# 3_esc_power_sw.net
KiCad netlist of a schematic drawn in Altium Designer
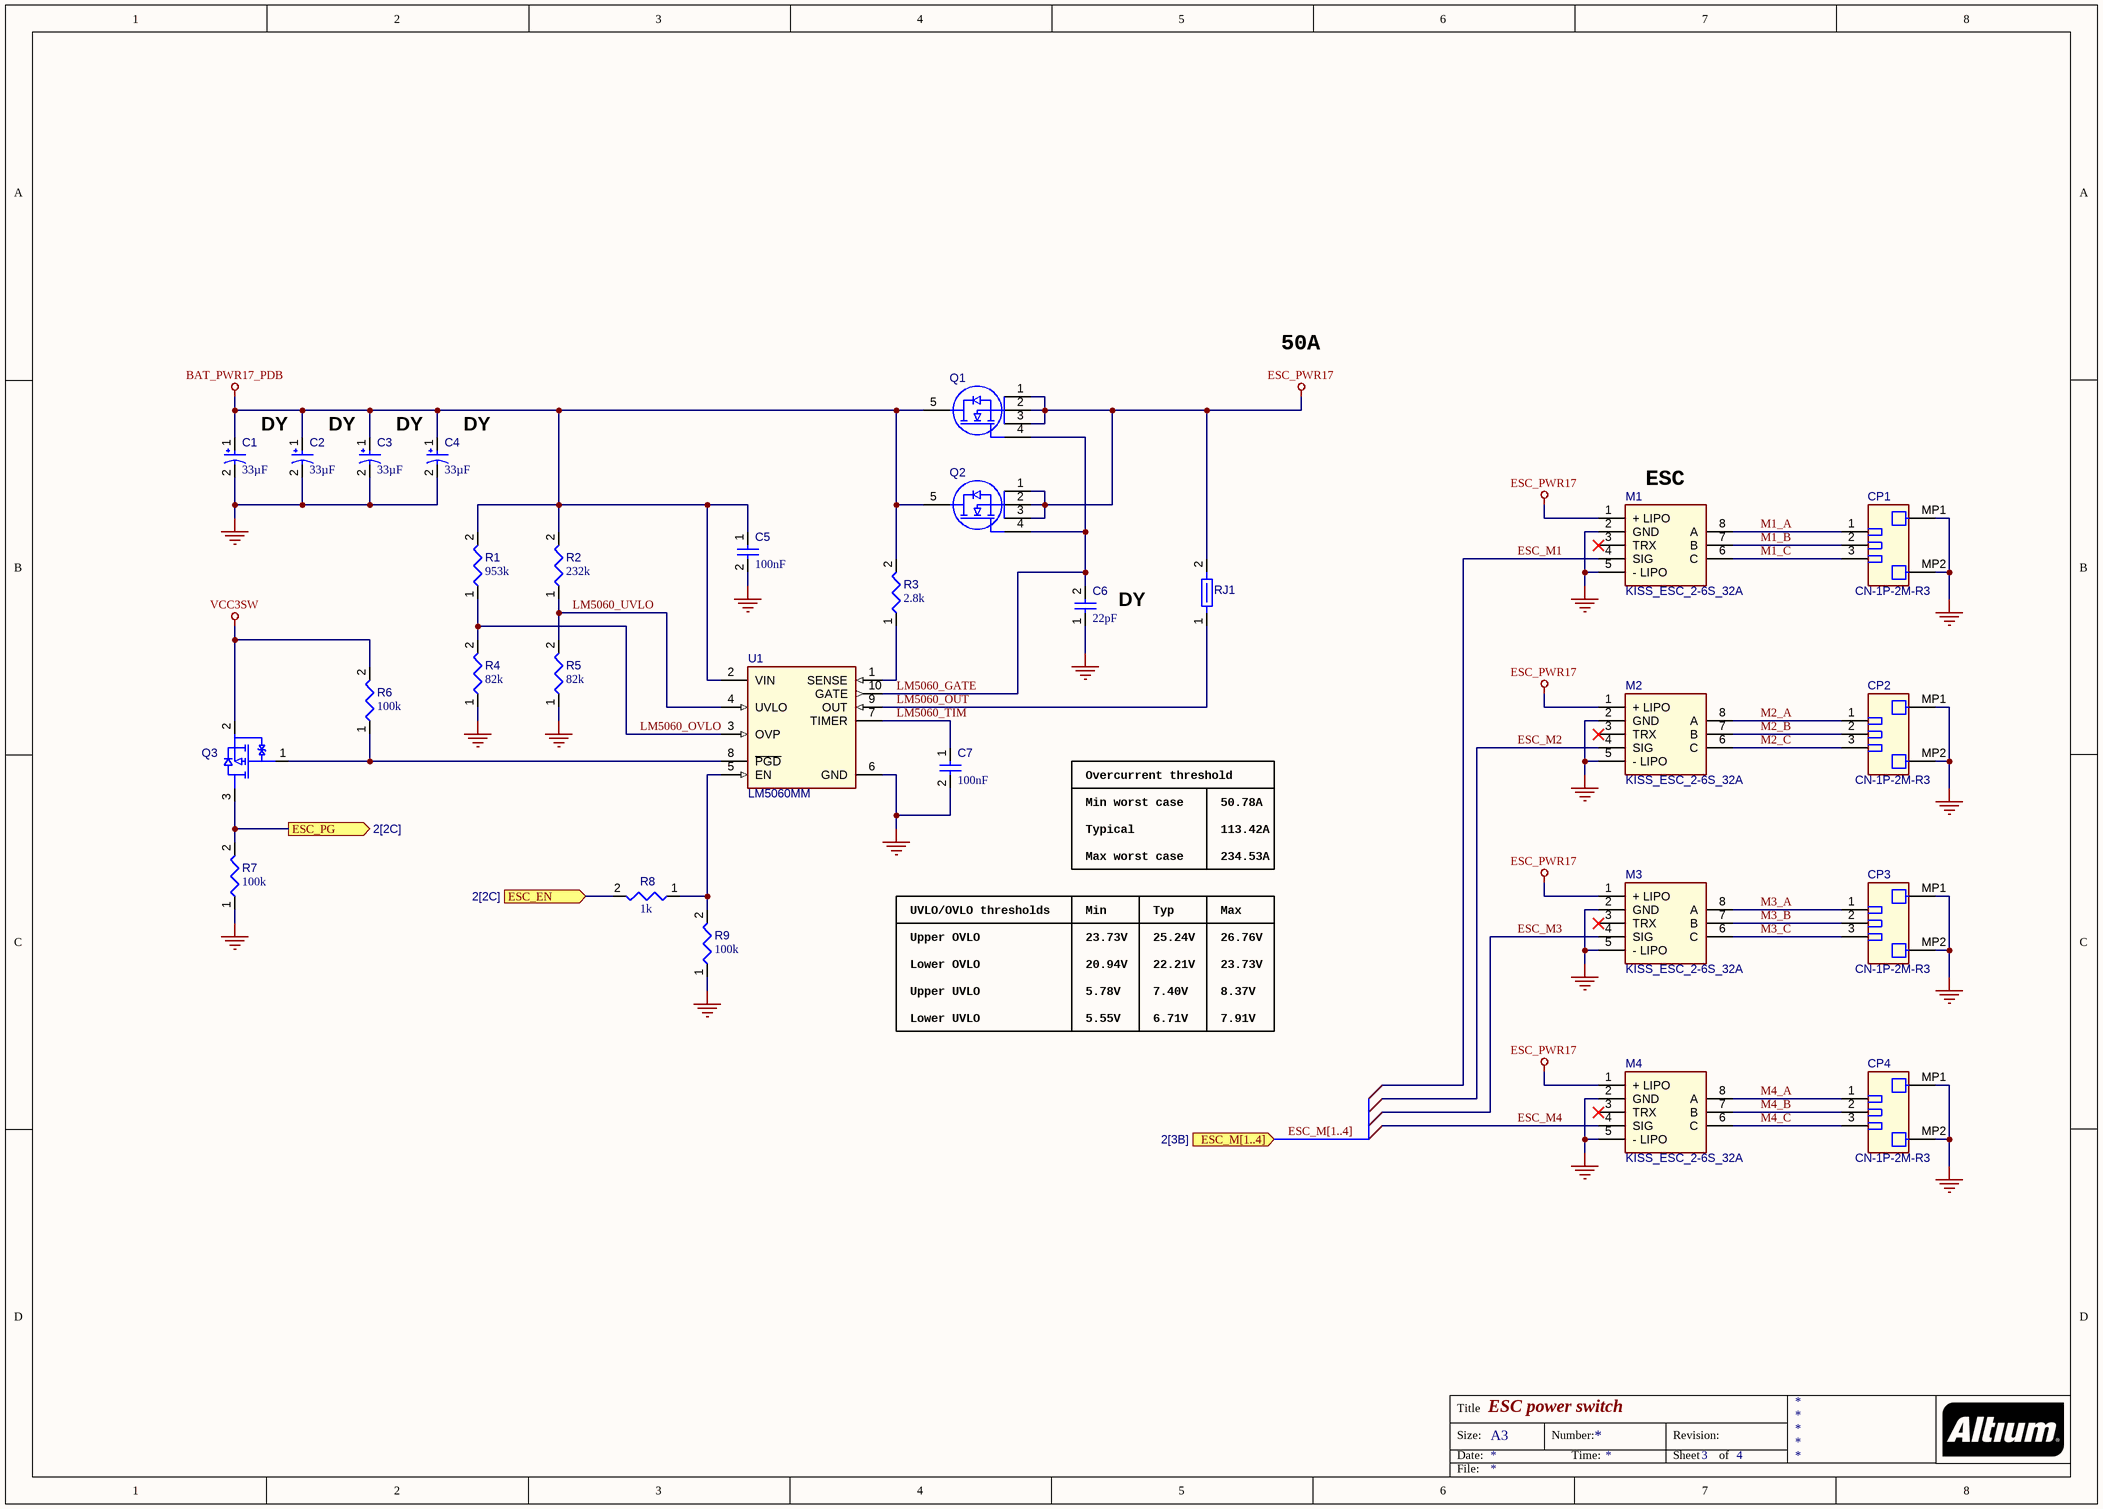
[diagram p0: 3_esc_power_sw.SchDoc]

(export (version "E")
  (design (tool "Eeschema 10.0.6"))
  (components
    (comp (ref "C1")
      (value "33µF")
      (footprint "EEF-CX1E330R-Footprint-1")
      (description "Aluminum Organic Polymer Capacitors 33uF 25volt SP-Cap AEC-Q200")
      (fields (field (name "TOLERANCE") "20%") (field (name "Comment") "Capacitor 33µF +/-20% 25V 2917"))
      (libsource (lib "<Company> Server") (part "CAP-P-2"))
    )
    (comp (ref "C2")
      (value "33µF")
      (footprint "EEF-CX1E330R-Footprint-1")
      (description "Aluminum Organic Polymer Capacitors 33uF 25volt SP-Cap AEC-Q200")
      (fields (field (name "TOLERANCE") "20%") (field (name "Comment") "Capacitor 33µF +/-20% 25V 2917"))
      (libsource (lib "<Company> Server") (part "CAP-P-2"))
    )
    (comp (ref "C3")
      (value "33µF")
      (footprint "EEF-CX1E330R-Footprint-1")
      (description "Aluminum Organic Polymer Capacitors 33uF 25volt SP-Cap AEC-Q200")
      (fields (field (name "TOLERANCE") "20%") (field (name "Comment") "Capacitor 33µF +/-20% 25V 2917"))
      (libsource (lib "<Company> Server") (part "CAP-P-2"))
    )
    (comp (ref "C4")
      (value "33µF")
      (footprint "EEF-CX1E330R-Footprint-1")
      (description "Aluminum Organic Polymer Capacitors 33uF 25volt SP-Cap AEC-Q200")
      (fields (field (name "TOLERANCE") "20%") (field (name "Comment") "Capacitor 33µF +/-20% 25V 2917"))
      (libsource (lib "<Company> Server") (part "CAP-P-2"))
    )
    (comp (ref "C5")
      (value "100nF")
      (footprint "CAPC0402(1005)60_L")
      (description "Chip Capacitor, 100nF +/-20%, 50V, 0402, Thickness 0.6 mm")
      (fields (field (name "TOLERANCE") "10%") (field (name "Comment") "Capacitor 100nF +/-20% 50V 0402"))
      (libsource (lib "<Company> Server") (part "CAP-NP-2"))
    )
    (comp (ref "C6")
      (value "22pF")
      (footprint "CAPC0402(1005)60_L")
      (description "Chip Capacitor, 22pF +/-10%, 50V, 0402, Thickness 0.6 mm")
      (fields (field (name "TOLERANCE") "10%") (field (name "Comment") "Capacitor 22pF +/-10% 50V 0402"))
      (libsource (lib "<Company> Server") (part "CAP-NP-2"))
    )
    (comp (ref "C7")
      (value "100nF")
      (footprint "CAPC0402(1005)60_L")
      (description "Chip Capacitor, 100nF +/-20%, 50V, 0402, Thickness 0.6 mm")
      (fields (field (name "TOLERANCE") "10%") (field (name "Comment") "Capacitor 100nF +/-20% 50V 0402"))
      (libsource (lib "<Company> Server") (part "CAP-NP-2"))
    )
    (comp (ref "CP1")
      (value "CN-1P-2M-R3")
      (footprint "MR30PW-FB-Footprint-1")
      (description "AMASS 500V 15A   0.8 mOhm")
      (libsource (lib "<Company> Server") (part "CMP-001-0016-5"))
    )
    (comp (ref "CP2")
      (value "CN-1P-2M-R3")
      (footprint "MR30PW-FB-Footprint-1")
      (description "AMASS 500V 15A   0.8 mOhm")
      (libsource (lib "<Company> Server") (part "CMP-001-0016-5"))
    )
    (comp (ref "CP3")
      (value "CN-1P-2M-R3")
      (footprint "MR30PW-FB-Footprint-1")
      (description "AMASS 500V 15A   0.8 mOhm")
      (libsource (lib "<Company> Server") (part "CMP-001-0016-5"))
    )
    (comp (ref "CP4")
      (value "CN-1P-2M-R3")
      (footprint "MR30PW-FB-Footprint-1")
      (description "AMASS 500V 15A   0.8 mOhm")
      (libsource (lib "<Company> Server") (part "CMP-001-0016-5"))
    )
    (comp (ref "M1")
      (value "KISS_ESC_2-6S_32A")
      (footprint "ESC 2-6S 32A-Footprint-1")
      (description "KISS ESC 2-6S 32A (45A limit) - 32bit brushless Motor Ctrl")
      (libsource (lib "<Company> Server") (part "CMP-001-0017-10"))
    )
    (comp (ref "M2")
      (value "KISS_ESC_2-6S_32A")
      (footprint "ESC 2-6S 32A-Footprint-1")
      (description "KISS ESC 2-6S 32A (45A limit) - 32bit brushless Motor Ctrl")
      (libsource (lib "<Company> Server") (part "CMP-001-0017-10"))
    )
    (comp (ref "M3")
      (value "KISS_ESC_2-6S_32A")
      (footprint "ESC 2-6S 32A-Footprint-1")
      (description "KISS ESC 2-6S 32A (45A limit) - 32bit brushless Motor Ctrl")
      (libsource (lib "<Company> Server") (part "CMP-001-0017-10"))
    )
    (comp (ref "M4")
      (value "KISS_ESC_2-6S_32A")
      (footprint "ESC 2-6S 32A-Footprint-1")
      (description "KISS ESC 2-6S 32A (45A limit) - 32bit brushless Motor Ctrl")
      (libsource (lib "<Company> Server") (part "CMP-001-0017-10"))
    )
    (comp (ref "Q1")
      (value "PSMN1R0-30YLDX")
      (footprint "NXP-SOT669_L")
      (description "N-channel Logic Level MOSFET, 30 V, 300 A, -55 to 175 degC, 5-Pin SOT669, RoHS, Tape and Reel")
      (libsource (lib "<Company> Server") (part "CMP-00089-6"))
    )
    (comp (ref "Q2")
      (value "PSMN1R0-30YLDX")
      (footprint "NXP-SOT669_L")
      (description "N-channel Logic Level MOSFET, 30 V, 300 A, -55 to 175 degC, 5-Pin SOT669, RoHS, Tape and Reel")
      (libsource (lib "<Company> Server") (part "CMP-00089-6"))
    )
    (comp (ref "Q3")
      (value "RZM002P02T2L")
      (footprint "ROHM-SOT723-3_V")
      (description "Pch Small Signal MOSFET, 20 V, 200 mA, 3-Pin SOT723, RoHS, Tape and Reel")
      (libsource (lib "<Company> Server") (part "CMP-00006-6"))
    )
    (comp (ref "R1")
      (value "953k")
      (footprint "RESC0402(1005)_L")
      (description "Chip Resistor, 953 kOhms, +/-1 %, 63 mW, -55 to 155 degC, 0402")
      (fields (field (name "POWER") "63mW") (field (name "TOLERANCE") "1%"))
      (libsource (lib "<Company> Server") (part "RES-2"))
    )
    (comp (ref "R2")
      (value "232k")
      (footprint "RESC0402(1005)_L")
      (description "Chip Resistor, 232 kOhms, +/-1 %, 63 mW, -55 to 155 degC, 0402")
      (fields (field (name "TOLERANCE") "1%") (field (name "POWER") "63mW"))
      (libsource (lib "<Company> Server") (part "RES-2"))
    )
    (comp (ref "R3")
      (value "2.8k")
      (footprint "RESC0402(1005)_L")
      (description "Chip Resistor, 2,8 kOhms, +/-1 %, 63 mW, -55 to 155 degC, 0402")
      (fields (field (name "POWER") "63mW") (field (name "TOLERANCE") "1%"))
      (libsource (lib "<Company> Server") (part "RES-2"))
    )
    (comp (ref "R4")
      (value "82k")
      (footprint "RESC0402(1005)_L")
      (description "Chip Resistor, 82 kOhms, +/-1 %, 63 mW, -55 to 155 degC, 0402")
      (fields (field (name "TOLERANCE") "1%") (field (name "POWER") "63mW"))
      (libsource (lib "<Company> Server") (part "RES-2"))
    )
    (comp (ref "R5")
      (value "82k")
      (footprint "RESC0402(1005)_L")
      (description "Chip Resistor, 82 kOhms, +/-1 %, 63 mW, -55 to 155 degC, 0402")
      (fields (field (name "TOLERANCE") "1%") (field (name "POWER") "63mW"))
      (libsource (lib "<Company> Server") (part "RES-2"))
    )
    (comp (ref "R6")
      (value "100k")
      (footprint "RESC0402(1005)_L")
      (description "Chip Resistor, 100 kOhms, +/-1 %, 63 mW, -55 to 155 degC, 0402")
      (fields (field (name "TOLERANCE") "1%") (field (name "POWER") "63mW"))
      (libsource (lib "<Company> Server") (part "RES-2"))
    )
    (comp (ref "R7")
      (value "100k")
      (footprint "RESC0402(1005)_L")
      (description "Chip Resistor, 100 kOhms, +/-1 %, 63 mW, -55 to 155 degC, 0402")
      (fields (field (name "TOLERANCE") "1%") (field (name "POWER") "63mW"))
      (libsource (lib "<Company> Server") (part "RES-2"))
    )
    (comp (ref "R8")
      (value "1k")
      (footprint "RESC0402(1005)_L")
      (description "Chip Resistor, 1 kOhms, +/-5 %, 63 mW, -55 to 155 degC, 0402")
      (fields (field (name "TOLERANCE") "5%") (field (name "POWER") "63mW"))
      (libsource (lib "<Company> Server") (part "RES-2"))
    )
    (comp (ref "R9")
      (value "100k")
      (footprint "RESC0402(1005)_L")
      (description "Chip Resistor, 100 kOhms, +/-1 %, 63 mW, -55 to 155 degC, 0402")
      (fields (field (name "TOLERANCE") "1%") (field (name "POWER") "63mW"))
      (libsource (lib "<Company> Server") (part "RES-2"))
    )
    (comp (ref "RJ1")
      (value "Net Tie 10x8mil")
      (footprint "New footprint 1")
      (libsource (lib "<Company> Server") (part "CMP-00022-00002-2"))
    )
    (comp (ref "U1")
      (value "LM5060MM")
      (footprint "DGS0010A_N")
      (libsource (lib "<Company> Server") (part "CMP-00082-3"))
    )
  )
  (nets
    (net (code "1") (name "/ESC_EN") (class "Default")
      (node (ref "R8") (pin "2") (pinfunction "2_2") (pintype "passive"))
    )
    (net (code "2") (name "/ESC_M1") (class "Default")
      (node (ref "M1") (pin "4") (pinfunction "SIG_4") (pintype "passive"))
    )
    (net (code "3") (name "/ESC_M2") (class "Default")
      (node (ref "M2") (pin "4") (pinfunction "SIG_4") (pintype "passive"))
    )
    (net (code "4") (name "/ESC_M3") (class "Default")
      (node (ref "M3") (pin "4") (pinfunction "SIG_4") (pintype "passive"))
    )
    (net (code "5") (name "/ESC_M4") (class "Default")
      (node (ref "M4") (pin "4") (pinfunction "SIG_4") (pintype "passive"))
    )
    (net (code "7") (name "/ESC_PG") (class "Default")
      (node (ref "Q3") (pin "3") (pinfunction "D_3") (pintype "passive"))
      (node (ref "R7") (pin "2") (pinfunction "2_2") (pintype "passive"))
    )
    (net (code "8") (name "/LM5060_GATE") (class "Default")
      (node (ref "C6") (pin "2") (pinfunction "2_2") (pintype "passive"))
      (node (ref "Q1") (pin "4") (pinfunction "G_4") (pintype "passive"))
      (node (ref "Q2") (pin "4") (pinfunction "G_4") (pintype "passive"))
      (node (ref "U1") (pin "10") (pinfunction "GATE_10") (pintype "output"))
    )
    (net (code "9") (name "/LM5060_OUT") (class "Default")
      (node (ref "RJ1") (pin "1") (pinfunction "1_1") (pintype "passive"))
      (node (ref "U1") (pin "9") (pinfunction "OUT_9") (pintype "input"))
    )
    (net (code "10") (name "/LM5060_OVLO") (class "Default")
      (node (ref "R1") (pin "1") (pinfunction "1_1") (pintype "passive"))
      (node (ref "R4") (pin "2") (pinfunction "2_2") (pintype "passive"))
      (node (ref "U1") (pin "3") (pinfunction "OVP_3") (pintype "input"))
    )
    (net (code "11") (name "/LM5060_TIM") (class "Default")
      (node (ref "C7") (pin "1") (pinfunction "1_1") (pintype "passive"))
      (node (ref "U1") (pin "7") (pinfunction "TIMER_7") (pintype "passive"))
    )
    (net (code "12") (name "/LM5060_UVLO") (class "Default")
      (node (ref "R2") (pin "1") (pinfunction "1_1") (pintype "passive"))
      (node (ref "R5") (pin "2") (pinfunction "2_2") (pintype "passive"))
      (node (ref "U1") (pin "4") (pinfunction "UVLO_4") (pintype "input"))
    )
    (net (code "13") (name "/M1_A") (class "Default")
      (node (ref "CP1") (pin "1") (pinfunction "1_1") (pintype "passive"))
      (node (ref "M1") (pin "8") (pinfunction "A_8") (pintype "passive"))
    )
    (net (code "14") (name "/M1_B") (class "Default")
      (node (ref "CP1") (pin "2") (pinfunction "2_2") (pintype "passive"))
      (node (ref "M1") (pin "7") (pinfunction "B_7") (pintype "passive"))
    )
    (net (code "15") (name "/M1_C") (class "Default")
      (node (ref "CP1") (pin "3") (pinfunction "3_3") (pintype "passive"))
      (node (ref "M1") (pin "6") (pinfunction "C_6") (pintype "passive"))
    )
    (net (code "16") (name "/M2_A") (class "Default")
      (node (ref "CP2") (pin "1") (pinfunction "1_1") (pintype "passive"))
      (node (ref "M2") (pin "8") (pinfunction "A_8") (pintype "passive"))
    )
    (net (code "17") (name "/M2_B") (class "Default")
      (node (ref "CP2") (pin "2") (pinfunction "2_2") (pintype "passive"))
      (node (ref "M2") (pin "7") (pinfunction "B_7") (pintype "passive"))
    )
    (net (code "18") (name "/M2_C") (class "Default")
      (node (ref "CP2") (pin "3") (pinfunction "3_3") (pintype "passive"))
      (node (ref "M2") (pin "6") (pinfunction "C_6") (pintype "passive"))
    )
    (net (code "19") (name "/M3_A") (class "Default")
      (node (ref "CP3") (pin "1") (pinfunction "1_1") (pintype "passive"))
      (node (ref "M3") (pin "8") (pinfunction "A_8") (pintype "passive"))
    )
    (net (code "20") (name "/M3_B") (class "Default")
      (node (ref "CP3") (pin "2") (pinfunction "2_2") (pintype "passive"))
      (node (ref "M3") (pin "7") (pinfunction "B_7") (pintype "passive"))
    )
    (net (code "21") (name "/M3_C") (class "Default")
      (node (ref "CP3") (pin "3") (pinfunction "3_3") (pintype "passive"))
      (node (ref "M3") (pin "6") (pinfunction "C_6") (pintype "passive"))
    )
    (net (code "22") (name "/M4_A") (class "Default")
      (node (ref "CP4") (pin "1") (pinfunction "1_1") (pintype "passive"))
      (node (ref "M4") (pin "8") (pinfunction "A_8") (pintype "passive"))
    )
    (net (code "23") (name "/M4_B") (class "Default")
      (node (ref "CP4") (pin "2") (pinfunction "2_2") (pintype "passive"))
      (node (ref "M4") (pin "7") (pinfunction "B_7") (pintype "passive"))
    )
    (net (code "24") (name "/M4_C") (class "Default")
      (node (ref "CP4") (pin "3") (pinfunction "3_3") (pintype "passive"))
      (node (ref "M4") (pin "6") (pinfunction "C_6") (pintype "passive"))
    )
    (net (code "25") (name "BAT_PWR17_PDB") (class "Default")
      (node (ref "C1") (pin "1") (pinfunction "1_1") (pintype "passive"))
      (node (ref "C2") (pin "1") (pinfunction "1_1") (pintype "passive"))
      (node (ref "C3") (pin "1") (pinfunction "1_1") (pintype "passive"))
      (node (ref "C4") (pin "1") (pinfunction "1_1") (pintype "passive"))
      (node (ref "C5") (pin "1") (pinfunction "1_1") (pintype "passive"))
      (node (ref "Q1") (pin "5") (pinfunction "D_5") (pintype "passive"))
      (node (ref "Q2") (pin "5") (pinfunction "D_5") (pintype "passive"))
      (node (ref "R1") (pin "2") (pinfunction "2_2") (pintype "passive"))
      (node (ref "R2") (pin "2") (pinfunction "2_2") (pintype "passive"))
      (node (ref "R3") (pin "2") (pinfunction "2_2") (pintype "passive"))
      (node (ref "U1") (pin "2") (pinfunction "VIN_2") (pintype "power_in"))
    )
    (net (code "26") (name "ESC_PWR17") (class "Default")
      (node (ref "M1") (pin "1") (pinfunction "+_LIPO_1") (pintype "passive"))
      (node (ref "M2") (pin "1") (pinfunction "+_LIPO_1") (pintype "passive"))
      (node (ref "M3") (pin "1") (pinfunction "+_LIPO_1") (pintype "passive"))
      (node (ref "M4") (pin "1") (pinfunction "+_LIPO_1") (pintype "passive"))
      (node (ref "Q1") (pin "1") (pinfunction "S_1") (pintype "passive"))
      (node (ref "Q1") (pin "2") (pinfunction "S_2") (pintype "passive"))
      (node (ref "Q1") (pin "3") (pinfunction "S_3") (pintype "passive"))
      (node (ref "Q2") (pin "1") (pinfunction "S_1") (pintype "passive"))
      (node (ref "Q2") (pin "2") (pinfunction "S_2") (pintype "passive"))
      (node (ref "Q2") (pin "3") (pinfunction "S_3") (pintype "passive"))
      (node (ref "RJ1") (pin "2") (pinfunction "2_2") (pintype "passive"))
    )
    (net (code "27") (name "GND") (class "Default")
      (node (ref "C1") (pin "2") (pinfunction "2_2") (pintype "passive"))
      (node (ref "C2") (pin "2") (pinfunction "2_2") (pintype "passive"))
      (node (ref "C3") (pin "2") (pinfunction "2_2") (pintype "passive"))
      (node (ref "C4") (pin "2") (pinfunction "2_2") (pintype "passive"))
      (node (ref "C5") (pin "2") (pinfunction "2_2") (pintype "passive"))
      (node (ref "C6") (pin "1") (pinfunction "1_1") (pintype "passive"))
      (node (ref "C7") (pin "2") (pinfunction "2_2") (pintype "passive"))
      (node (ref "CP1") (pin "MP1") (pinfunction "MP1_MP1") (pintype "passive"))
      (node (ref "CP1") (pin "MP2") (pinfunction "MP2_MP2") (pintype "passive"))
      (node (ref "CP2") (pin "MP1") (pinfunction "MP1_MP1") (pintype "passive"))
      (node (ref "CP2") (pin "MP2") (pinfunction "MP2_MP2") (pintype "passive"))
      (node (ref "CP3") (pin "MP1") (pinfunction "MP1_MP1") (pintype "passive"))
      (node (ref "CP3") (pin "MP2") (pinfunction "MP2_MP2") (pintype "passive"))
      (node (ref "CP4") (pin "MP1") (pinfunction "MP1_MP1") (pintype "passive"))
      (node (ref "CP4") (pin "MP2") (pinfunction "MP2_MP2") (pintype "passive"))
      (node (ref "M1") (pin "2") (pinfunction "GND_2") (pintype "passive"))
      (node (ref "M1") (pin "5") (pinfunction "-_LIPO_5") (pintype "passive"))
      (node (ref "M2") (pin "2") (pinfunction "GND_2") (pintype "passive"))
      (node (ref "M2") (pin "5") (pinfunction "-_LIPO_5") (pintype "passive"))
      (node (ref "M3") (pin "2") (pinfunction "GND_2") (pintype "passive"))
      (node (ref "M3") (pin "5") (pinfunction "-_LIPO_5") (pintype "passive"))
      (node (ref "M4") (pin "2") (pinfunction "GND_2") (pintype "passive"))
      (node (ref "M4") (pin "5") (pinfunction "-_LIPO_5") (pintype "passive"))
      (node (ref "R4") (pin "1") (pinfunction "1_1") (pintype "passive"))
      (node (ref "R5") (pin "1") (pinfunction "1_1") (pintype "passive"))
      (node (ref "R7") (pin "1") (pinfunction "1_1") (pintype "passive"))
      (node (ref "R9") (pin "1") (pinfunction "1_1") (pintype "passive"))
      (node (ref "U1") (pin "6") (pinfunction "GND_6") (pintype "power_in"))
    )
    (net (code "28") (name "Net-(Q3-G)") (class "Default")
      (node (ref "Q3") (pin "1") (pinfunction "G_1") (pintype "passive"))
      (node (ref "R6") (pin "1") (pinfunction "1_1") (pintype "passive"))
      (node (ref "U1") (pin "8") (pinfunction "~{PGD}_8") (pintype "open_collector"))
    )
    (net (code "29") (name "Net-(U1-EN)") (class "Default")
      (node (ref "R8") (pin "1") (pinfunction "1_1") (pintype "passive"))
      (node (ref "R9") (pin "2") (pinfunction "2_2") (pintype "passive"))
      (node (ref "U1") (pin "5") (pinfunction "EN_5") (pintype "input"))
    )
    (net (code "30") (name "Net-(U1-SENSE)") (class "Default")
      (node (ref "R3") (pin "1") (pinfunction "1_1") (pintype "passive"))
      (node (ref "U1") (pin "1") (pinfunction "SENSE_1") (pintype "input"))
    )
    (net (code "31") (name "VCC3SW") (class "Default")
      (node (ref "Q3") (pin "2") (pinfunction "S_2") (pintype "passive"))
      (node (ref "R6") (pin "2") (pinfunction "2_2") (pintype "passive"))
    )
    (net (code "32") (name "unconnected-(M1-TRX-Pad3)") (class "Default")
      (node (ref "M1") (pin "3") (pinfunction "TRX_3") (pintype "passive+no_connect"))
    )
    (net (code "33") (name "unconnected-(M2-TRX-Pad3)") (class "Default")
      (node (ref "M2") (pin "3") (pinfunction "TRX_3") (pintype "passive+no_connect"))
    )
    (net (code "34") (name "unconnected-(M3-TRX-Pad3)") (class "Default")
      (node (ref "M3") (pin "3") (pinfunction "TRX_3") (pintype "passive+no_connect"))
    )
    (net (code "35") (name "unconnected-(M4-TRX-Pad3)") (class "Default")
      (node (ref "M4") (pin "3") (pinfunction "TRX_3") (pintype "passive+no_connect"))
    )
  )
)
